# ProPrj_ABRGBDRV_MK_I_2025-07-25.net
KiCad netlist of a schematic drawn in EasyEDA Pro
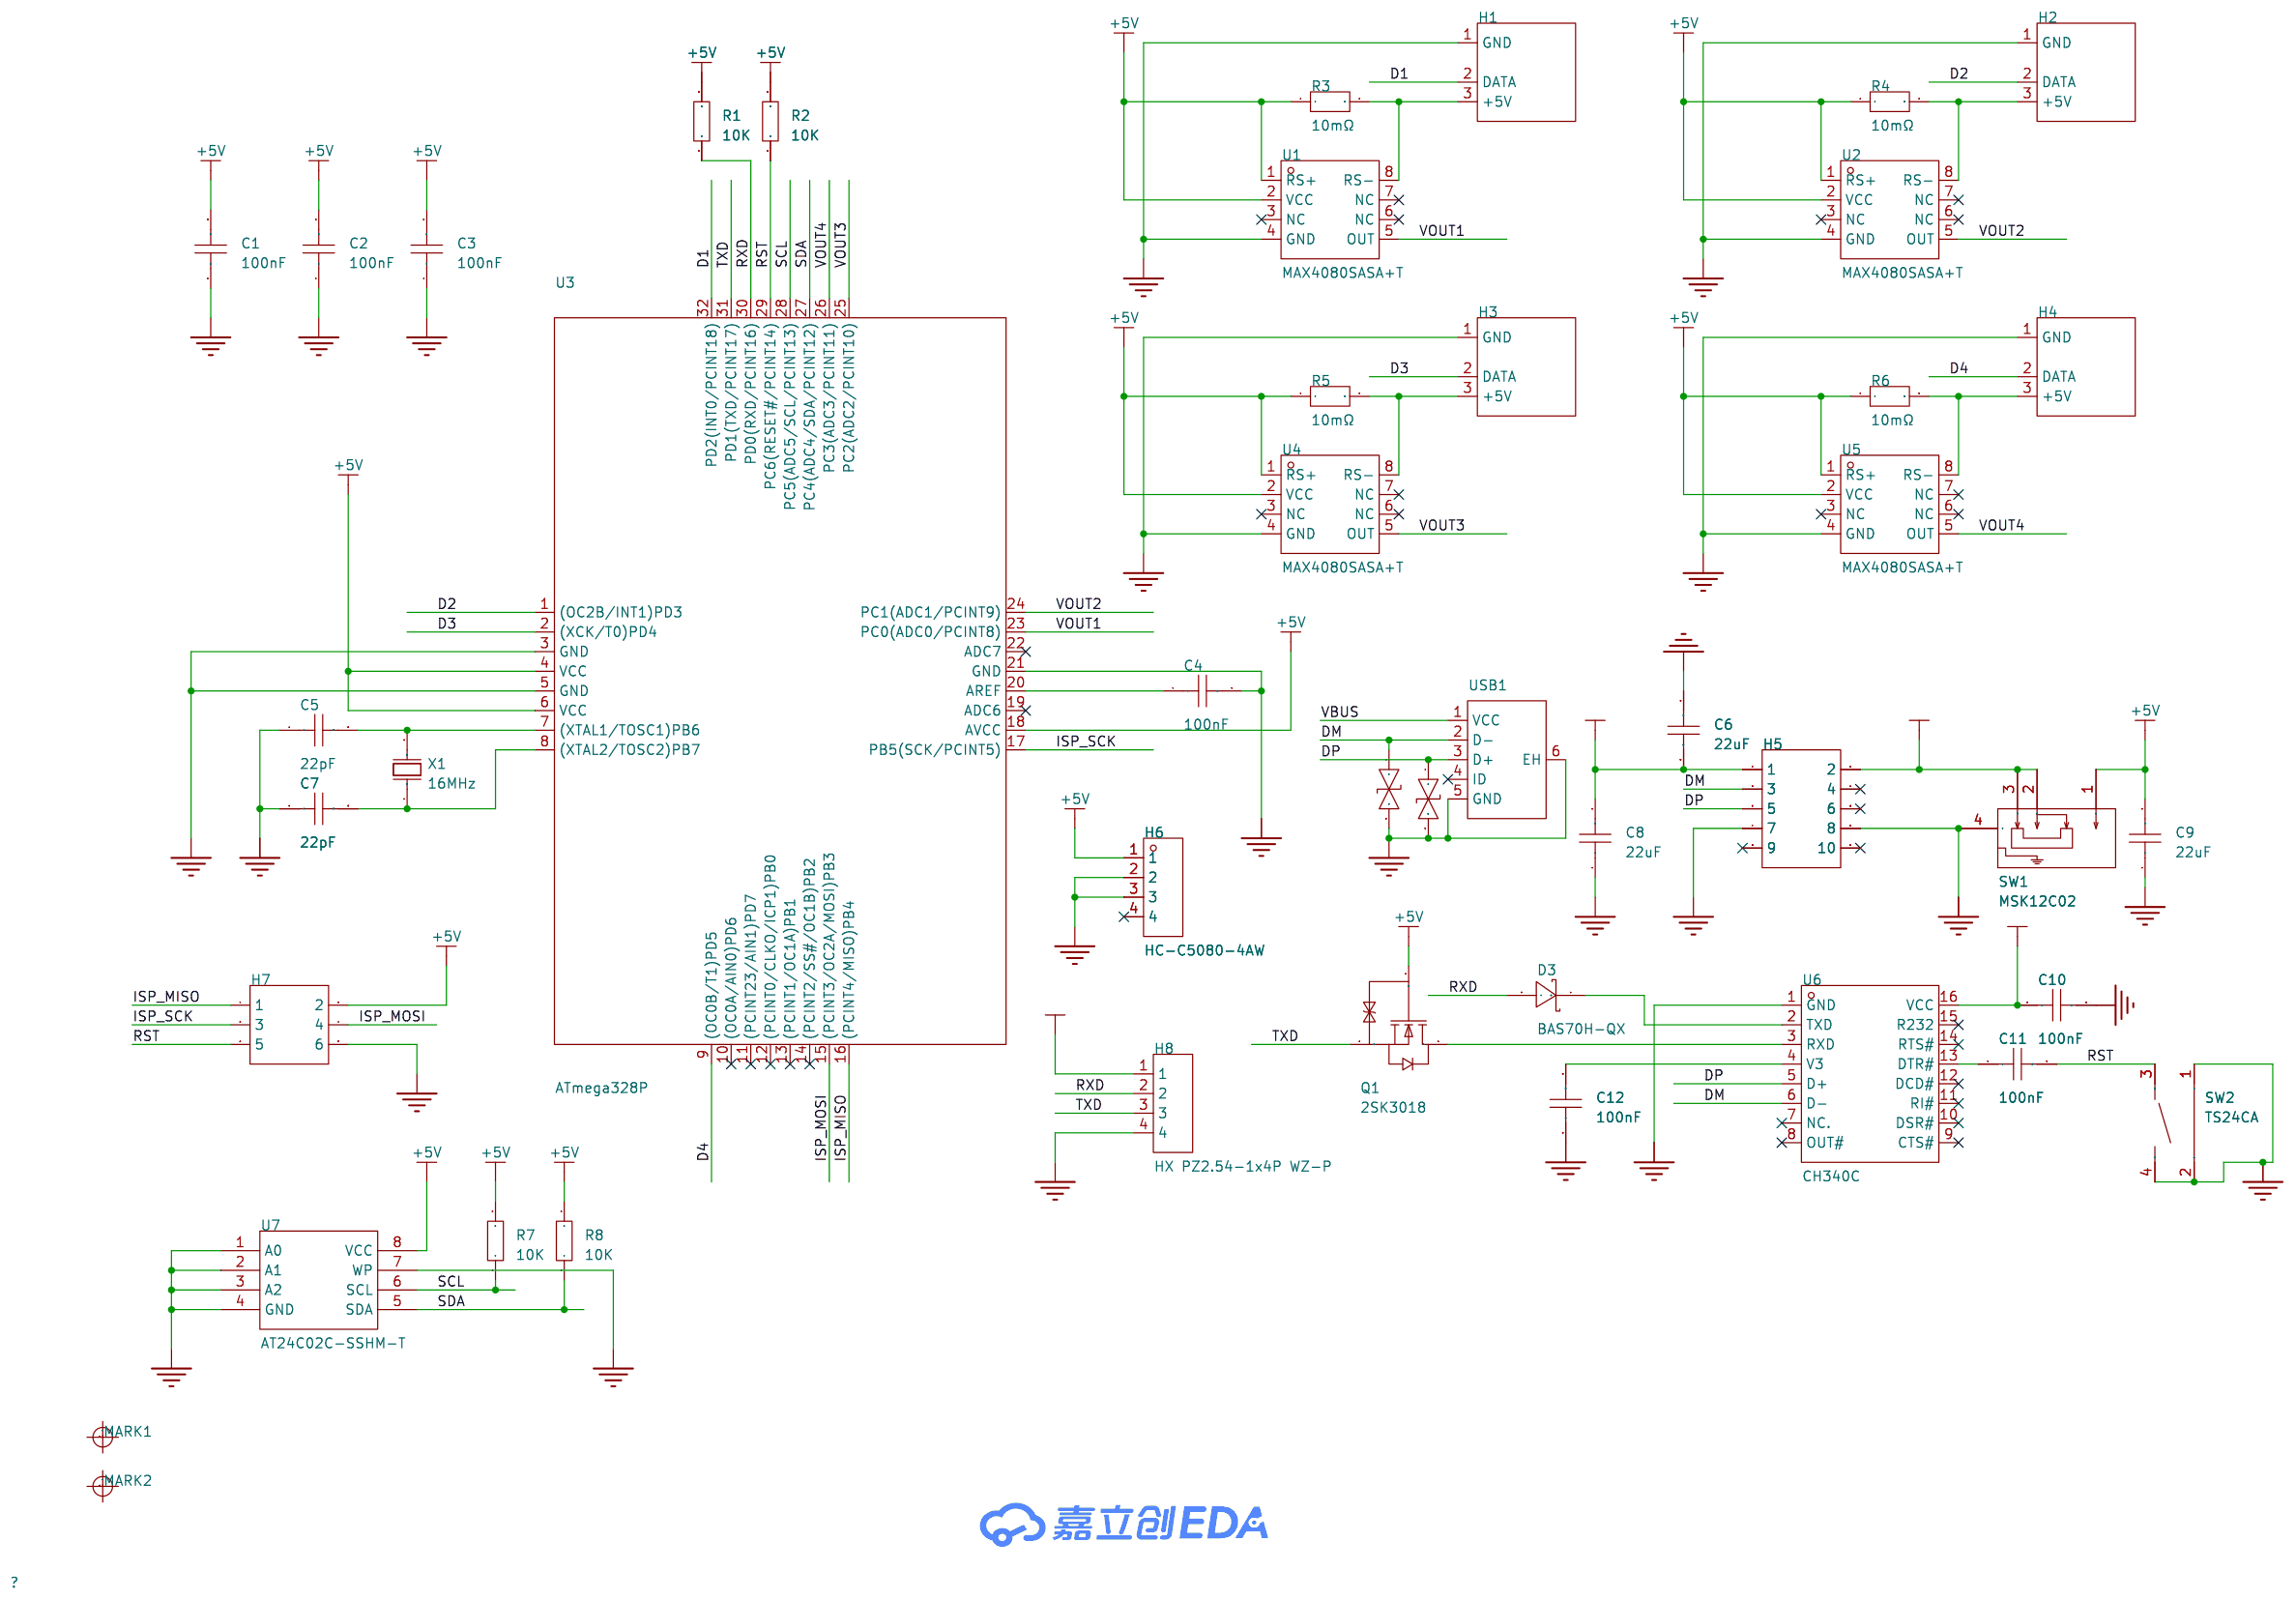
[diagram p0: schematic sheet]

(export (version "E")
  (design (tool "Eeschema 10.0.6"))
  (components
    (comp (ref "C1")
      (value "100nF")
      (footprint "easyedapro:C0603")
      (libsource (lib "easyedapro") (part "CapAcitance"))
    )
    (comp (ref "C2")
      (value "100nF")
      (footprint "easyedapro:C0603")
      (libsource (lib "easyedapro") (part "CapAcitance"))
    )
    (comp (ref "C3")
      (value "100nF")
      (footprint "easyedapro:C0603")
      (libsource (lib "easyedapro") (part "CapAcitance"))
    )
    (comp (ref "C4")
      (value "100nF")
      (footprint "easyedapro:C0603")
      (libsource (lib "easyedapro") (part "CapAcitance"))
    )
    (comp (ref "C5")
      (value "22pF")
      (footprint "easyedapro:C0603")
      (libsource (lib "easyedapro") (part "CapAcitance"))
    )
    (comp (ref "C6")
      (value "22uF")
      (footprint "easyedapro:C0603")
      (libsource (lib "easyedapro") (part "CapAcitance"))
    )
    (comp (ref "C7")
      (value "22pF")
      (footprint "easyedapro:C0603")
      (libsource (lib "easyedapro") (part "CapAcitance"))
    )
    (comp (ref "C8")
      (value "22uF")
      (footprint "easyedapro:C0603")
      (libsource (lib "easyedapro") (part "CapAcitance"))
    )
    (comp (ref "C9")
      (value "22uF")
      (footprint "easyedapro:C0603")
      (libsource (lib "easyedapro") (part "CapAcitance"))
    )
    (comp (ref "C10")
      (value "100nF")
      (footprint "easyedapro:C0603")
      (libsource (lib "easyedapro") (part "CapAcitance"))
    )
    (comp (ref "C11")
      (value "100nF")
      (footprint "easyedapro:C0603")
      (libsource (lib "easyedapro") (part "CapAcitance"))
    )
    (comp (ref "C12")
      (value "100nF")
      (footprint "easyedapro:C0603")
      (libsource (lib "easyedapro") (part "CapAcitance"))
    )
    (comp (ref "D1")
      (value "0402ESDA-05N")
      (fields (field (name "Manufacturer") "BORN(伯恩半导体)"))
      (libsource (lib "easyedapro") (part "0402ESDA-05N"))
    )
    (comp (ref "D2")
      (value "0402ESDA-05N")
      (fields (field (name "Manufacturer") "BORN(伯恩半导体)"))
      (libsource (lib "easyedapro") (part "0402ESDA-05N"))
    )
    (comp (ref "D3")
      (value "BAS70H-QX")
      (footprint "easyedapro:SOD-123_L2.6-W1.6-LS3.5-RD")
      (fields (field (name "Manufacturer") "Nexperia(安世)"))
      (libsource (lib "easyedapro") (part "BAS70H-QX"))
    )
    (comp (ref "H1")
      (value "~")
      (footprint "easyedapro:ARGB TH_3P-P2.54 弯针")
      (libsource (lib "easyedapro") (part "ARGB 弯针"))
    )
    (comp (ref "H2")
      (value "~")
      (footprint "easyedapro:ARGB TH_3P-P2.54 弯针")
      (libsource (lib "easyedapro") (part "ARGB 弯针"))
    )
    (comp (ref "H3")
      (value "~")
      (footprint "easyedapro:ARGB TH_3P-P2.54 弯针")
      (libsource (lib "easyedapro") (part "ARGB 弯针"))
    )
    (comp (ref "H4")
      (value "~")
      (footprint "easyedapro:ARGB TH_3P-P2.54 弯针")
      (libsource (lib "easyedapro") (part "ARGB 弯针"))
    )
    (comp (ref "H5")
      (value "~")
      (footprint "easyedapro:HDR-TH_10P-P2.54-V-F-R2-C5-S2.54")
      (libsource (lib "easyedapro") (part "HDR-F-2.54_2x5"))
    )
    (comp (ref "H6")
      (value "HC-C5080-4AW")
      (footprint "easyedapro:CONN-TH_4P-P5.08_HCTL_HC-C5080-4AW")
      (fields (field (name "Manufacturer") "HCTL(华灿天禄)"))
      (libsource (lib "easyedapro") (part "HC-C5080-4AW"))
    )
    (comp (ref "H7")
      (value "~")
      (footprint "easyedapro:HDR-TH_6P-P2.54-V-R2-C3-S2.54_A2541WV-2X3P")
      (libsource (lib "easyedapro") (part "HDR-M-2.54_2x3"))
    )
    (comp (ref "H8")
      (value "HX PZ2.54-1x4P WZ-P")
      (footprint "easyedapro:HDR-TH_4P-P2.54-H-M-W11.0")
      (fields (field (name "Manufacturer") "hanxia(韩下)"))
      (libsource (lib "easyedapro") (part "HX PZ2.54-1X4P WZ-P"))
    )
    (comp (ref "MARK1")
      (value "~")
      (footprint "easyedapro:Mark-Point-1mm")
      (description "Mark点")
      (libsource (lib "easyedapro") (part "Mark-Point"))
    )
    (comp (ref "MARK2")
      (value "~")
      (footprint "easyedapro:Mark-Point-1mm")
      (description "Mark点")
      (libsource (lib "easyedapro") (part "Mark-Point"))
    )
    (comp (ref "Q1")
      (value "2SK3018")
      (footprint "easyedapro:SOT-23-3_L2.9-W1.4-P1.90-LS2.6-BR")
      (fields (field (name "Manufacturer") "TWGMC(台湾迪嘉)"))
      (libsource (lib "easyedapro") (part "2SK3018_C727148"))
    )
    (comp (ref "R1") (value "10K") (footprint "easyedapro:R0805") (libsource (lib "easyedapro") (part "电阻")))
    (comp (ref "R2") (value "10K") (footprint "easyedapro:R0805") (libsource (lib "easyedapro") (part "电阻")))
    (comp (ref "R3")
      (value "10mΩ")
      (footprint "easyedapro:R2512")
      (description "电阻类型:采样电阻;阻值:10mΩ;精度:±1%;功率:3W;温度系数:±50ppm/°C;")
      (fields (field (name "Manufacturer Part") "RE2512F3R010") (field (name "Manufacturer") "捷而瑞"))
      (libsource (lib "easyedapro") (part "RE2512F3R010"))
    )
    (comp (ref "R4")
      (value "10mΩ")
      (footprint "easyedapro:R2512")
      (description "电阻类型:采样电阻;阻值:10mΩ;精度:±1%;功率:3W;温度系数:±50ppm/°C;")
      (fields (field (name "Manufacturer Part") "RE2512F3R010") (field (name "Manufacturer") "捷而瑞"))
      (libsource (lib "easyedapro") (part "RE2512F3R010"))
    )
    (comp (ref "R5")
      (value "10mΩ")
      (footprint "easyedapro:R2512")
      (description "电阻类型:采样电阻;阻值:10mΩ;精度:±1%;功率:3W;温度系数:±50ppm/°C;")
      (fields (field (name "Manufacturer Part") "RE2512F3R010") (field (name "Manufacturer") "捷而瑞"))
      (libsource (lib "easyedapro") (part "RE2512F3R010"))
    )
    (comp (ref "R6")
      (value "10mΩ")
      (footprint "easyedapro:R2512")
      (description "电阻类型:采样电阻;阻值:10mΩ;精度:±1%;功率:3W;温度系数:±50ppm/°C;")
      (fields (field (name "Manufacturer Part") "RE2512F3R010") (field (name "Manufacturer") "捷而瑞"))
      (libsource (lib "easyedapro") (part "RE2512F3R010"))
    )
    (comp (ref "R7") (value "10K") (footprint "easyedapro:R0805") (libsource (lib "easyedapro") (part "电阻")))
    (comp (ref "R8") (value "10K") (footprint "easyedapro:R0805") (libsource (lib "easyedapro") (part "电阻")))
    (comp (ref "SW1")
      (value "MSK12C02")
      (footprint "easyedapro:SW-TH_MSK12C02")
      (description "电路结构:单刀双掷;安装方式:卧贴;开关颜色:-;额定电流(DC):50mA;额定电压(DC):12V;额定电流(AC):-;额定电压(AC):-;机械寿命:1万次;")
      (fields (field (name "Manufacturer") "SHOU HAN(首韩)"))
      (libsource (lib "easyedapro") (part "MSK12C02"))
    )
    (comp (ref "SW2")
      (value "TS24CA")
      (footprint "easyedapro:SW-SMD_TS24CA")
      (description "电路结构:单刀单掷;按钮形状:矩形按钮;安装方式:卧贴;开关长度:4.55mm;开关宽度:1.8mm;开关高度:3.5mm;触点电流:50mA;额定电压:12V;带灯:-;工作寿命:-;")
      (fields (field (name "Manufacturer") "SHOU HAN(首韩)"))
      (libsource (lib "easyedapro") (part "TS24CA"))
    )
    (comp (ref "U1")
      (value "MAX4080SASA+T")
      (footprint "easyedapro:SOP-8_L4.9-W3.9-P1.27-LS6.0-BL")
      (description "放大器数:单路;共模电压:4.5V~76V;增益:60V/V;带宽:250kHz;")
      (fields (field (name "Manufacturer") "ADI(亚德诺)/MAXIM(美信)"))
      (libsource (lib "easyedapro") (part "MAX4080SASA+T"))
    )
    (comp (ref "U2")
      (value "MAX4080SASA+T")
      (footprint "easyedapro:SOP-8_L4.9-W3.9-P1.27-LS6.0-BL")
      (description "放大器数:单路;共模电压:4.5V~76V;增益:60V/V;带宽:250kHz;")
      (fields (field (name "Manufacturer") "ADI(亚德诺)/MAXIM(美信)"))
      (libsource (lib "easyedapro") (part "MAX4080SASA+T"))
    )
    (comp (ref "U3")
      (value "ATmega328P")
      (footprint "easyedapro:LQFP-32_L7.0-W7.0-P0.80-LS9.0-TL")
      (libsource (lib "easyedapro") (part "ATMEGA328P"))
    )
    (comp (ref "U4")
      (value "MAX4080SASA+T")
      (footprint "easyedapro:SOP-8_L4.9-W3.9-P1.27-LS6.0-BL")
      (description "放大器数:单路;共模电压:4.5V~76V;增益:60V/V;带宽:250kHz;")
      (fields (field (name "Manufacturer") "ADI(亚德诺)/MAXIM(美信)"))
      (libsource (lib "easyedapro") (part "MAX4080SASA+T"))
    )
    (comp (ref "U5")
      (value "MAX4080SASA+T")
      (footprint "easyedapro:SOP-8_L4.9-W3.9-P1.27-LS6.0-BL")
      (description "放大器数:单路;共模电压:4.5V~76V;增益:60V/V;带宽:250kHz;")
      (fields (field (name "Manufacturer") "ADI(亚德诺)/MAXIM(美信)"))
      (libsource (lib "easyedapro") (part "MAX4080SASA+T"))
    )
    (comp (ref "U6")
      (value "CH340C")
      (footprint "easyedapro:SOP-16_L10.0-W3.9-P1.27-LS6.0-BL")
      (description "应用功能:收发器;接口协议:USB 2.0;数据速率:2Mbps;")
      (fields (field (name "Manufacturer") "WCH(南京沁恒)"))
      (libsource (lib "easyedapro") (part "CH340C"))
    )
    (comp (ref "U7")
      (value "AT24C02C-SSHM-T")
      (footprint "easyedapro:SOIC-8_L5.0-W4.0-P1.27-LS6.0-BL")
      (description "接口类型:I2C;存储容量:2Kbit;")
      (fields (field (name "Manufacturer") "MICROCHIP(美国微芯)"))
      (libsource (lib "easyedapro") (part "AT24C02C-SSHM-T"))
    )
    (comp (ref "USB1")
      (value "~")
      (footprint "easyedapro:USB_Micro")
      (libsource (lib "easyedapro") (part "USB_Micro"))
    )
    (comp (ref "X1")
      (value "16MHz")
      (footprint "easyedapro:CRYSTAL-TH_L11.1-W4.7-P4.88")
      (description "晶振类型:-;频率:16MHz;常温频差:±20ppm;负载电容:20pF;频率稳定度:±30ppm;")
      (fields (field (name "Manufacturer Part") "SCBYS16X00000ELRJ") (field (name "Manufacturer") "SST(索斯特)"))
      (libsource (lib "easyedapro") (part "SCBYS16X00000ELRJ"))
    )
  )
  (nets
    (net (code "1") (name "+5V") (class "Default")
      (node (ref "C1") (pin "2") (pinfunction "2_2") (pintype "input"))
      (node (ref "C2") (pin "2") (pinfunction "2_2") (pintype "input"))
      (node (ref "C3") (pin "2") (pinfunction "2_2") (pintype "input"))
      (node (ref "C9") (pin "2") (pinfunction "2_2") (pintype "input"))
      (node (ref "H6") (pin "1") (pinfunction "1_1") (pintype "unspecified"))
      (node (ref "H7") (pin "2") (pinfunction "2_2") (pintype "input"))
      (node (ref "Q1") (pin "1") (pinfunction "G_1") (pintype "unspecified"))
      (node (ref "R1") (pin "2") (pinfunction "2_2") (pintype "input"))
      (node (ref "R2") (pin "2") (pinfunction "2_2") (pintype "input"))
      (node (ref "R3") (pin "1") (pinfunction "1_1") (pintype "unspecified"))
      (node (ref "R4") (pin "1") (pinfunction "1_1") (pintype "unspecified"))
      (node (ref "R5") (pin "1") (pinfunction "1_1") (pintype "unspecified"))
      (node (ref "R6") (pin "1") (pinfunction "1_1") (pintype "unspecified"))
      (node (ref "R7") (pin "2") (pinfunction "2_2") (pintype "input"))
      (node (ref "R8") (pin "2") (pinfunction "2_2") (pintype "input"))
      (node (ref "SW1") (pin "1") (pinfunction "1_1") (pintype "unspecified"))
      (node (ref "U1") (pin "1") (pinfunction "RS+_1") (pintype "unspecified"))
      (node (ref "U1") (pin "2") (pinfunction "VCC_2") (pintype "unspecified"))
      (node (ref "U2") (pin "1") (pinfunction "RS+_1") (pintype "unspecified"))
      (node (ref "U2") (pin "2") (pinfunction "VCC_2") (pintype "unspecified"))
      (node (ref "U3") (pin "18") (pinfunction "AVCC_18") (pintype "unspecified"))
      (node (ref "U3") (pin "4") (pinfunction "VCC_4") (pintype "unspecified"))
      (node (ref "U3") (pin "6") (pinfunction "VCC_6") (pintype "unspecified"))
      (node (ref "U4") (pin "1") (pinfunction "RS+_1") (pintype "unspecified"))
      (node (ref "U4") (pin "2") (pinfunction "VCC_2") (pintype "unspecified"))
      (node (ref "U5") (pin "1") (pinfunction "RS+_1") (pintype "unspecified"))
      (node (ref "U5") (pin "2") (pinfunction "VCC_2") (pintype "unspecified"))
      (node (ref "U7") (pin "8") (pinfunction "VCC_8") (pintype "unspecified"))
    )
    (net (code "2") (name "/D1") (class "Default")
      (node (ref "H1") (pin "2") (pinfunction "DATA_2") (pintype "unspecified"))
      (node (ref "U3") (pin "32") (pinfunction "PD2(INT0/PCINT18)_32") (pintype "unspecified"))
    )
    (net (code "3") (name "/D2") (class "Default")
      (node (ref "H2") (pin "2") (pinfunction "DATA_2") (pintype "unspecified"))
      (node (ref "U3") (pin "1") (pinfunction "(OC2B/INT1)PD3_1") (pintype "unspecified"))
    )
    (net (code "4") (name "/D3") (class "Default")
      (node (ref "H3") (pin "2") (pinfunction "DATA_2") (pintype "unspecified"))
      (node (ref "U3") (pin "2") (pinfunction "(XCK/T0)PD4_2") (pintype "unspecified"))
    )
    (net (code "5") (name "/D4") (class "Default")
      (node (ref "H4") (pin "2") (pinfunction "DATA_2") (pintype "unspecified"))
      (node (ref "U3") (pin "9") (pinfunction "(OC0B/T1)PD5_9") (pintype "unspecified"))
    )
    (net (code "6") (name "/DM") (class "Default")
      (node (ref "D1") (pin "1") (pinfunction "1_1") (pintype "input"))
      (node (ref "H5") (pin "3") (pinfunction "3_3") (pintype "input"))
      (node (ref "U6") (pin "6") (pinfunction "D-_6") (pintype "unspecified"))
      (node (ref "USB1") (pin "2") (pinfunction "D-_2") (pintype "input"))
    )
    (net (code "7") (name "/DP") (class "Default")
      (node (ref "D2") (pin "1") (pinfunction "1_1") (pintype "input"))
      (node (ref "H5") (pin "5") (pinfunction "5_5") (pintype "input"))
      (node (ref "U6") (pin "5") (pinfunction "D+_5") (pintype "unspecified"))
      (node (ref "USB1") (pin "3") (pinfunction "D+_3") (pintype "input"))
    )
    (net (code "8") (name "/ISP_MISO") (class "Default")
      (node (ref "H7") (pin "1") (pinfunction "1_1") (pintype "input"))
      (node (ref "U3") (pin "16") (pinfunction "(PCINT4/MISO)PB4_16") (pintype "unspecified"))
    )
    (net (code "9") (name "/ISP_MOSI") (class "Default")
      (node (ref "H7") (pin "4") (pinfunction "4_4") (pintype "input"))
      (node (ref "U3") (pin "15") (pinfunction "(PCINT3/OC2A/MOSI)PB3_15") (pintype "unspecified"))
    )
    (net (code "10") (name "/ISP_SCK") (class "Default")
      (node (ref "H7") (pin "3") (pinfunction "3_3") (pintype "input"))
      (node (ref "U3") (pin "17") (pinfunction "PB5(SCK/PCINT5)_17") (pintype "unspecified"))
    )
    (net (code "11") (name "/RST") (class "Default")
      (node (ref "C11") (pin "2") (pinfunction "2_2") (pintype "input"))
      (node (ref "H7") (pin "5") (pinfunction "5_5") (pintype "input"))
      (node (ref "R2") (pin "1") (pinfunction "1_1") (pintype "input"))
      (node (ref "SW2") (pin "3") (pinfunction "3_3") (pintype "unspecified"))
      (node (ref "U3") (pin "29") (pinfunction "PC6(RESET#/PCINT14)_29") (pintype "unspecified"))
    )
    (net (code "12") (name "/RXD") (class "Default")
      (node (ref "D3") (pin "2") (pinfunction "A_2") (pintype "unspecified"))
      (node (ref "H8") (pin "2") (pinfunction "2_2") (pintype "unspecified"))
      (node (ref "R1") (pin "1") (pinfunction "1_1") (pintype "input"))
      (node (ref "U3") (pin "30") (pinfunction "PD0(RXD/PCINT16)_30") (pintype "unspecified"))
    )
    (net (code "13") (name "/SCL") (class "Default")
      (node (ref "R7") (pin "1") (pinfunction "1_1") (pintype "input"))
      (node (ref "U3") (pin "28") (pinfunction "PC5(ADC5/SCL/PCINT13)_28") (pintype "unspecified"))
      (node (ref "U7") (pin "6") (pinfunction "SCL_6") (pintype "unspecified"))
    )
    (net (code "14") (name "/SDA") (class "Default")
      (node (ref "R8") (pin "1") (pinfunction "1_1") (pintype "input"))
      (node (ref "U3") (pin "27") (pinfunction "PC4(ADC4/SDA/PCINT12)_27") (pintype "unspecified"))
      (node (ref "U7") (pin "5") (pinfunction "SDA_5") (pintype "unspecified"))
    )
    (net (code "15") (name "/TXD") (class "Default")
      (node (ref "H8") (pin "3") (pinfunction "3_3") (pintype "unspecified"))
      (node (ref "Q1") (pin "2") (pinfunction "S_2") (pintype "unspecified"))
      (node (ref "U3") (pin "31") (pinfunction "PD1(TXD/PCINT17)_31") (pintype "unspecified"))
    )
    (net (code "16") (name "/VOUT1") (class "Default")
      (node (ref "U1") (pin "5") (pinfunction "OUT_5") (pintype "unspecified"))
      (node (ref "U3") (pin "23") (pinfunction "PC0(ADC0/PCINT8)_23") (pintype "unspecified"))
    )
    (net (code "17") (name "/VOUT2") (class "Default")
      (node (ref "U2") (pin "5") (pinfunction "OUT_5") (pintype "unspecified"))
      (node (ref "U3") (pin "24") (pinfunction "PC1(ADC1/PCINT9)_24") (pintype "unspecified"))
    )
    (net (code "18") (name "/VOUT3") (class "Default")
      (node (ref "U3") (pin "25") (pinfunction "PC2(ADC2/PCINT10)_25") (pintype "unspecified"))
      (node (ref "U4") (pin "5") (pinfunction "OUT_5") (pintype "unspecified"))
    )
    (net (code "19") (name "/VOUT4") (class "Default")
      (node (ref "U3") (pin "26") (pinfunction "PC3(ADC3/PCINT11)_26") (pintype "unspecified"))
      (node (ref "U5") (pin "5") (pinfunction "OUT_5") (pintype "unspecified"))
    )
    (net (code "20") (name "GND") (class "Default")
      (node (ref "C1") (pin "1") (pinfunction "1_1") (pintype "input"))
      (node (ref "C10") (pin "2") (pinfunction "2_2") (pintype "input"))
      (node (ref "C12") (pin "1") (pinfunction "1_1") (pintype "input"))
      (node (ref "C2") (pin "1") (pinfunction "1_1") (pintype "input"))
      (node (ref "C3") (pin "1") (pinfunction "1_1") (pintype "input"))
      (node (ref "C4") (pin "2") (pinfunction "2_2") (pintype "input"))
      (node (ref "C5") (pin "1") (pinfunction "1_1") (pintype "input"))
      (node (ref "C6") (pin "1") (pinfunction "1_1") (pintype "input"))
      (node (ref "C7") (pin "1") (pinfunction "1_1") (pintype "input"))
      (node (ref "C8") (pin "1") (pinfunction "1_1") (pintype "input"))
      (node (ref "C9") (pin "1") (pinfunction "1_1") (pintype "input"))
      (node (ref "D1") (pin "2") (pinfunction "2_2") (pintype "input"))
      (node (ref "D2") (pin "2") (pinfunction "2_2") (pintype "input"))
      (node (ref "H1") (pin "1") (pinfunction "GND_1") (pintype "unspecified"))
      (node (ref "H2") (pin "1") (pinfunction "GND_1") (pintype "unspecified"))
      (node (ref "H3") (pin "1") (pinfunction "GND_1") (pintype "unspecified"))
      (node (ref "H4") (pin "1") (pinfunction "GND_1") (pintype "unspecified"))
      (node (ref "H5") (pin "7") (pinfunction "7_7") (pintype "input"))
      (node (ref "H5") (pin "8") (pinfunction "8_8") (pintype "input"))
      (node (ref "H6") (pin "2") (pinfunction "2_2") (pintype "unspecified"))
      (node (ref "H6") (pin "3") (pinfunction "3_3") (pintype "unspecified"))
      (node (ref "H7") (pin "6") (pinfunction "6_6") (pintype "input"))
      (node (ref "H8") (pin "4") (pinfunction "4_4") (pintype "unspecified"))
      (node (ref "SW1") (pin "4") (pinfunction "4_4") (pintype "unspecified"))
      (node (ref "SW2") (pin "1") (pinfunction "1_1") (pintype "unspecified"))
      (node (ref "SW2") (pin "2") (pinfunction "2_2") (pintype "unspecified"))
      (node (ref "SW2") (pin "4") (pinfunction "4_4") (pintype "unspecified"))
      (node (ref "U1") (pin "4") (pinfunction "GND_4") (pintype "unspecified"))
      (node (ref "U2") (pin "4") (pinfunction "GND_4") (pintype "unspecified"))
      (node (ref "U3") (pin "21") (pinfunction "GND_21") (pintype "unspecified"))
      (node (ref "U3") (pin "3") (pinfunction "GND_3") (pintype "unspecified"))
      (node (ref "U3") (pin "5") (pinfunction "GND_5") (pintype "unspecified"))
      (node (ref "U4") (pin "4") (pinfunction "GND_4") (pintype "unspecified"))
      (node (ref "U5") (pin "4") (pinfunction "GND_4") (pintype "unspecified"))
      (node (ref "U6") (pin "1") (pinfunction "GND_1") (pintype "unspecified"))
      (node (ref "U7") (pin "1") (pinfunction "A0_1") (pintype "unspecified"))
      (node (ref "U7") (pin "2") (pinfunction "A1_2") (pintype "unspecified"))
      (node (ref "U7") (pin "3") (pinfunction "A2_3") (pintype "unspecified"))
      (node (ref "U7") (pin "4") (pinfunction "GND_4") (pintype "unspecified"))
      (node (ref "U7") (pin "7") (pinfunction "WP_7") (pintype "unspecified"))
      (node (ref "USB1") (pin "5") (pinfunction "GND_5") (pintype "input"))
      (node (ref "USB1") (pin "6") (pinfunction "EH_6") (pintype "input"))
    )
    (net (code "21") (name "Net-(D3-C)") (class "Default")
      (node (ref "D3") (pin "1") (pinfunction "C_1") (pintype "unspecified"))
      (node (ref "U6") (pin "2") (pinfunction "TXD_2") (pintype "unspecified"))
    )
    (net (code "22") (name "Net-(H1-+5V)") (class "Default")
      (node (ref "H1") (pin "3") (pinfunction "+5V_3") (pintype "unspecified"))
      (node (ref "R3") (pin "2") (pinfunction "2_2") (pintype "unspecified"))
      (node (ref "U1") (pin "8") (pinfunction "RS-_8") (pintype "unspecified"))
    )
    (net (code "23") (name "Net-(H2-+5V)") (class "Default")
      (node (ref "H2") (pin "3") (pinfunction "+5V_3") (pintype "unspecified"))
      (node (ref "R4") (pin "2") (pinfunction "2_2") (pintype "unspecified"))
      (node (ref "U2") (pin "8") (pinfunction "RS-_8") (pintype "unspecified"))
    )
    (net (code "24") (name "Net-(H3-+5V)") (class "Default")
      (node (ref "H3") (pin "3") (pinfunction "+5V_3") (pintype "unspecified"))
      (node (ref "R5") (pin "2") (pinfunction "2_2") (pintype "unspecified"))
      (node (ref "U4") (pin "8") (pinfunction "RS-_8") (pintype "unspecified"))
    )
    (net (code "25") (name "Net-(H4-+5V)") (class "Default")
      (node (ref "H4") (pin "3") (pinfunction "+5V_3") (pintype "unspecified"))
      (node (ref "R6") (pin "2") (pinfunction "2_2") (pintype "unspecified"))
      (node (ref "U5") (pin "8") (pinfunction "RS-_8") (pintype "unspecified"))
    )
    (net (code "26") (name "Net-(Q1-D)") (class "Default")
      (node (ref "Q1") (pin "3") (pinfunction "D_3") (pintype "unspecified"))
      (node (ref "U6") (pin "3") (pinfunction "RXD_3") (pintype "unspecified"))
    )
    (net (code "27") (name "Net-(U3-(XTAL1{slash}TOSC1)PB6)") (class "Default")
      (node (ref "C5") (pin "2") (pinfunction "2_2") (pintype "input"))
      (node (ref "U3") (pin "7") (pinfunction "(XTAL1/TOSC1)PB6_7") (pintype "unspecified"))
      (node (ref "X1") (pin "2") (pinfunction "OSC2_2") (pintype "input"))
    )
    (net (code "28") (name "Net-(U3-(XTAL2{slash}TOSC2)PB7)") (class "Default")
      (node (ref "C7") (pin "2") (pinfunction "2_2") (pintype "input"))
      (node (ref "U3") (pin "8") (pinfunction "(XTAL2/TOSC2)PB7_8") (pintype "unspecified"))
      (node (ref "X1") (pin "1") (pinfunction "OSC1_1") (pintype "input"))
    )
    (net (code "29") (name "Net-(U3-AREF)") (class "Default")
      (node (ref "C4") (pin "1") (pinfunction "1_1") (pintype "input"))
      (node (ref "U3") (pin "20") (pinfunction "AREF_20") (pintype "unspecified"))
    )
    (net (code "30") (name "Net-(U6-DTR#)") (class "Default")
      (node (ref "C11") (pin "1") (pinfunction "1_1") (pintype "input"))
      (node (ref "U6") (pin "13") (pinfunction "DTR#_13") (pintype "unspecified"))
    )
    (net (code "31") (name "Net-(U6-V3)") (class "Default")
      (node (ref "C12") (pin "2") (pinfunction "2_2") (pintype "input"))
      (node (ref "U6") (pin "4") (pinfunction "V3_4") (pintype "unspecified"))
    )
    (net (code "32") (name "VBUS") (class "Default")
      (node (ref "C10") (pin "1") (pinfunction "1_1") (pintype "input"))
      (node (ref "C6") (pin "2") (pinfunction "2_2") (pintype "input"))
      (node (ref "C8") (pin "2") (pinfunction "2_2") (pintype "input"))
      (node (ref "H5") (pin "1") (pinfunction "1_1") (pintype "input"))
      (node (ref "H5") (pin "2") (pinfunction "2_2") (pintype "input"))
      (node (ref "H8") (pin "1") (pinfunction "1_1") (pintype "unspecified"))
      (node (ref "SW1") (pin "2") (pinfunction "2_2") (pintype "unspecified"))
      (node (ref "SW1") (pin "3") (pinfunction "3_3") (pintype "unspecified"))
      (node (ref "U6") (pin "16") (pinfunction "VCC_16") (pintype "unspecified"))
      (node (ref "USB1") (pin "1") (pinfunction "VCC_1") (pintype "input"))
    )
    (net (code "33") (name "unconnected-(H5-Pad4)") (class "Default")
      (node (ref "H5") (pin "4") (pinfunction "4_4") (pintype "input+no_connect"))
    )
    (net (code "34") (name "unconnected-(H5-Pad6)") (class "Default")
      (node (ref "H5") (pin "6") (pinfunction "6_6") (pintype "input+no_connect"))
    )
    (net (code "35") (name "unconnected-(H5-Pad9)") (class "Default")
      (node (ref "H5") (pin "9") (pinfunction "9_9") (pintype "input+no_connect"))
    )
    (net (code "36") (name "unconnected-(H5-Pad10)") (class "Default")
      (node (ref "H5") (pin "10") (pinfunction "10_10") (pintype "input+no_connect"))
    )
    (net (code "37") (name "unconnected-(H6-Pad4)") (class "Default")
      (node (ref "H6") (pin "4") (pinfunction "4_4") (pintype "unspecified+no_connect"))
    )
    (net (code "38") (name "unconnected-(MARK1-Pad1)") (class "Default")
      (node (ref "MARK1") (pin "1") (pinfunction "1_1") (pintype "input"))
    )
    (net (code "39") (name "unconnected-(MARK2-Pad1)") (class "Default")
      (node (ref "MARK2") (pin "1") (pinfunction "1_1") (pintype "input"))
    )
    (net (code "40") (name "unconnected-(U1-NC-Pad3)") (class "Default")
      (node (ref "U1") (pin "3") (pinfunction "NC_3") (pintype "unspecified+no_connect"))
    )
    (net (code "41") (name "unconnected-(U1-NC-Pad6)") (class "Default")
      (node (ref "U1") (pin "6") (pinfunction "NC_6") (pintype "unspecified+no_connect"))
    )
    (net (code "42") (name "unconnected-(U1-NC-Pad7)") (class "Default")
      (node (ref "U1") (pin "7") (pinfunction "NC_7") (pintype "unspecified+no_connect"))
    )
    (net (code "43") (name "unconnected-(U2-NC-Pad3)") (class "Default")
      (node (ref "U2") (pin "3") (pinfunction "NC_3") (pintype "unspecified+no_connect"))
    )
    (net (code "44") (name "unconnected-(U2-NC-Pad6)") (class "Default")
      (node (ref "U2") (pin "6") (pinfunction "NC_6") (pintype "unspecified+no_connect"))
    )
    (net (code "45") (name "unconnected-(U2-NC-Pad7)") (class "Default")
      (node (ref "U2") (pin "7") (pinfunction "NC_7") (pintype "unspecified+no_connect"))
    )
    (net (code "46") (name "unconnected-(U3-(OC0A{slash}AIN0)PD6-Pad10)") (class "Default")
      (node (ref "U3") (pin "10") (pinfunction "(OC0A/AIN0)PD6_10") (pintype "unspecified+no_connect"))
    )
    (net (code "47") (name "unconnected-(U3-(PCINT0{slash}CLKO{slash}ICP1)PB0-Pad12)") (class "Default")
      (node (ref "U3") (pin "12") (pinfunction "(PCINT0/CLKO/ICP1)PB0_12") (pintype "unspecified+no_connect"))
    )
    (net (code "48") (name "unconnected-(U3-(PCINT1{slash}OC1A)PB1-Pad13)") (class "Default")
      (node (ref "U3") (pin "13") (pinfunction "(PCINT1/OC1A)PB1_13") (pintype "unspecified+no_connect"))
    )
    (net (code "49") (name "unconnected-(U3-(PCINT2{slash}SS#{slash}OC1B)PB2-Pad14)") (class "Default")
      (node (ref "U3") (pin "14") (pinfunction "(PCINT2/SS#/OC1B)PB2_14") (pintype "unspecified+no_connect"))
    )
    (net (code "50") (name "unconnected-(U3-(PCINT23{slash}AIN1)PD7-Pad11)") (class "Default")
      (node (ref "U3") (pin "11") (pinfunction "(PCINT23/AIN1)PD7_11") (pintype "unspecified+no_connect"))
    )
    (net (code "51") (name "unconnected-(U3-ADC6-Pad19)") (class "Default")
      (node (ref "U3") (pin "19") (pinfunction "ADC6_19") (pintype "unspecified+no_connect"))
    )
    (net (code "52") (name "unconnected-(U3-ADC7-Pad22)") (class "Default")
      (node (ref "U3") (pin "22") (pinfunction "ADC7_22") (pintype "unspecified+no_connect"))
    )
    (net (code "53") (name "unconnected-(U4-NC-Pad3)") (class "Default")
      (node (ref "U4") (pin "3") (pinfunction "NC_3") (pintype "unspecified+no_connect"))
    )
    (net (code "54") (name "unconnected-(U4-NC-Pad6)") (class "Default")
      (node (ref "U4") (pin "6") (pinfunction "NC_6") (pintype "unspecified+no_connect"))
    )
    (net (code "55") (name "unconnected-(U4-NC-Pad7)") (class "Default")
      (node (ref "U4") (pin "7") (pinfunction "NC_7") (pintype "unspecified+no_connect"))
    )
    (net (code "56") (name "unconnected-(U5-NC-Pad3)") (class "Default")
      (node (ref "U5") (pin "3") (pinfunction "NC_3") (pintype "unspecified+no_connect"))
    )
    (net (code "57") (name "unconnected-(U5-NC-Pad6)") (class "Default")
      (node (ref "U5") (pin "6") (pinfunction "NC_6") (pintype "unspecified+no_connect"))
    )
    (net (code "58") (name "unconnected-(U5-NC-Pad7)") (class "Default")
      (node (ref "U5") (pin "7") (pinfunction "NC_7") (pintype "unspecified+no_connect"))
    )
    (net (code "59") (name "unconnected-(U6-CTS#-Pad9)") (class "Default")
      (node (ref "U6") (pin "9") (pinfunction "CTS#_9") (pintype "unspecified+no_connect"))
    )
    (net (code "60") (name "unconnected-(U6-DCD#-Pad12)") (class "Default")
      (node (ref "U6") (pin "12") (pinfunction "DCD#_12") (pintype "unspecified+no_connect"))
    )
    (net (code "61") (name "unconnected-(U6-DSR#-Pad10)") (class "Default")
      (node (ref "U6") (pin "10") (pinfunction "DSR#_10") (pintype "unspecified+no_connect"))
    )
    (net (code "62") (name "unconnected-(U6-NC.-Pad7)") (class "Default")
      (node (ref "U6") (pin "7") (pinfunction "NC._7") (pintype "unspecified+no_connect"))
    )
    (net (code "63") (name "unconnected-(U6-OUT#-Pad8)") (class "Default")
      (node (ref "U6") (pin "8") (pinfunction "OUT#_8") (pintype "unspecified+no_connect"))
    )
    (net (code "64") (name "unconnected-(U6-R232-Pad15)") (class "Default")
      (node (ref "U6") (pin "15") (pinfunction "R232_15") (pintype "unspecified+no_connect"))
    )
    (net (code "65") (name "unconnected-(U6-RI#-Pad11)") (class "Default")
      (node (ref "U6") (pin "11") (pinfunction "RI#_11") (pintype "unspecified+no_connect"))
    )
    (net (code "66") (name "unconnected-(U6-RTS#-Pad14)") (class "Default")
      (node (ref "U6") (pin "14") (pinfunction "RTS#_14") (pintype "unspecified+no_connect"))
    )
    (net (code "67") (name "unconnected-(USB1-ID-Pad4)") (class "Default")
      (node (ref "USB1") (pin "4") (pinfunction "ID_4") (pintype "input+no_connect"))
    )
  )
)
